# Wash_Basin_Indicator.net
KiCad netlist of a schematic drawn in EAGLE
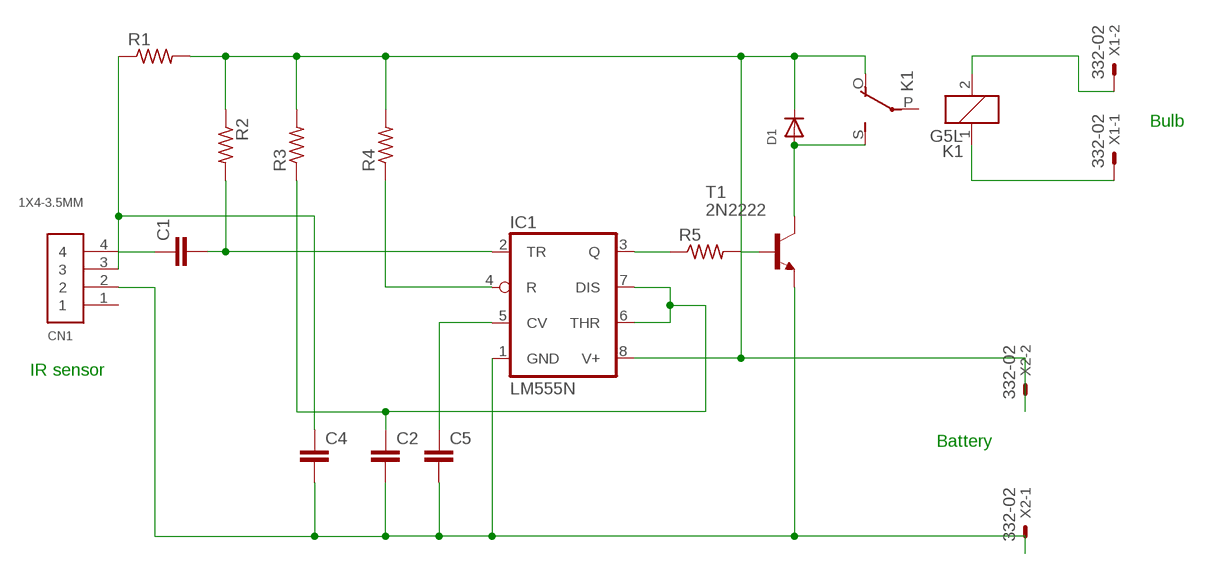
[diagram p0: schematic, sheet 1]

(export (version "E")
  (design (tool "Eeschema 10.0.6"))
  (components
    (comp (ref "C1")
      (value "C5/3.5")
      (footprint "eagle-import:C5B3.5")
      (libsource (lib "eagle-import") (part "C5/3.5"))
    )
    (comp (ref "C2")
      (value "C5/3.5")
      (footprint "eagle-import:C5B3.5")
      (libsource (lib "eagle-import") (part "C5/3.5"))
    )
    (comp (ref "C4")
      (value "C5/3.5")
      (footprint "eagle-import:C5B3.5")
      (libsource (lib "eagle-import") (part "C5/3.5"))
    )
    (comp (ref "C5")
      (value "C5/3.5")
      (footprint "eagle-import:C5B3.5")
      (libsource (lib "eagle-import") (part "C5/3.5"))
    )
    (comp (ref "CN1")
      (value "1X4-3.5MM")
      (footprint "eagle-import:1X04-3.5MM")
      (libsource (lib "eagle-import") (part "1X4-3.5MM"))
    )
    (comp (ref "D1")
      (value "DIODEDO-1N4148")
      (footprint "eagle-import:DO-1N4148")
      (libsource (lib "eagle-import") (part "DIODEDO-1N4148"))
    )
    (comp (ref "IC1")
      (value "LM555N")
      (footprint "eagle-import:DIL08")
      (libsource (lib "eagle-import") (part "555NLM"))
    )
    (comp (ref "K1")
      (value "G5L")
      (footprint "eagle-import:G5LE")
      (libsource (lib "eagle-import") (part "G5L"))
    )
    (comp (ref "R1")
      (value "R-US_0204/7")
      (footprint "eagle-import:0204_7")
      (libsource (lib "eagle-import") (part "R-US_0204/7"))
    )
    (comp (ref "R2")
      (value "R-US_0204/7")
      (footprint "eagle-import:0204_7")
      (libsource (lib "eagle-import") (part "R-US_0204/7"))
    )
    (comp (ref "R3")
      (value "R-US_0204/7")
      (footprint "eagle-import:0204_7")
      (libsource (lib "eagle-import") (part "R-US_0204/7"))
    )
    (comp (ref "R4")
      (value "R-US_0204/7")
      (footprint "eagle-import:0204_7")
      (libsource (lib "eagle-import") (part "R-US_0204/7"))
    )
    (comp (ref "R5")
      (value "R-US_0204/7")
      (footprint "eagle-import:0204_7")
      (libsource (lib "eagle-import") (part "R-US_0204/7"))
    )
    (comp (ref "T1")
      (value "2N2222")
      (footprint "eagle-import:TO92-EBC-OVAL")
      (libsource (lib "eagle-import") (part "2N2222"))
    )
    (comp (ref "X1")
      (value "332-02")
      (footprint "eagle-import:332-02")
      (libsource (lib "eagle-import") (part "332-02"))
    )
    (comp (ref "X2")
      (value "332-02")
      (footprint "eagle-import:332-02")
      (libsource (lib "eagle-import") (part "332-02"))
    )
  )
  (nets
    (net (code "1") (name "Net-(C1-Pad1)") (class "Default")
      (node (ref "C1") (pin "1") (pinfunction "1_1") (pintype "passive"))
      (node (ref "CN1") (pin "4") (pinfunction "4_4") (pintype "bidirectional"))
    )
    (net (code "2") (name "Net-(C4-Pad1)") (class "Default")
      (node (ref "C4") (pin "1") (pinfunction "1_1") (pintype "passive"))
      (node (ref "CN1") (pin "3") (pinfunction "3_3") (pintype "bidirectional"))
      (node (ref "R1") (pin "1") (pinfunction "1_1") (pintype "passive"))
    )
    (net (code "3") (name "Net-(D1-PadA)") (class "Default")
      (node (ref "D1") (pin "A") (pinfunction "A_A") (pintype "passive"))
      (node (ref "K1") (pin "S") (pinfunction "S_S") (pintype "passive"))
      (node (ref "T1") (pin "C") (pinfunction "C_C") (pintype "passive"))
    )
    (net (code "4") (name "Net-(IC1-CV)") (class "Default")
      (node (ref "C5") (pin "1") (pinfunction "1_1") (pintype "passive"))
      (node (ref "IC1") (pin "5") (pinfunction "CV_5") (pintype "input"))
    )
    (net (code "5") (name "Net-(IC1-DIS)") (class "Default")
      (node (ref "C2") (pin "1") (pinfunction "1_1") (pintype "passive"))
      (node (ref "IC1") (pin "6") (pinfunction "THR_6") (pintype "input"))
      (node (ref "IC1") (pin "7") (pinfunction "DIS_7") (pintype "input"))
      (node (ref "R3") (pin "1") (pinfunction "1_1") (pintype "passive"))
    )
    (net (code "6") (name "Net-(IC1-GND)") (class "Default")
      (node (ref "C2") (pin "2") (pinfunction "2_2") (pintype "passive"))
      (node (ref "C4") (pin "2") (pinfunction "2_2") (pintype "passive"))
      (node (ref "C5") (pin "2") (pinfunction "2_2") (pintype "passive"))
      (node (ref "CN1") (pin "2") (pinfunction "2_2") (pintype "bidirectional"))
      (node (ref "IC1") (pin "1") (pinfunction "GND_1") (pintype "power_in"))
      (node (ref "T1") (pin "E") (pinfunction "E_E") (pintype "passive"))
      (node (ref "X2") (pin "1") (pinfunction "S_1") (pintype "passive"))
    )
    (net (code "7") (name "Net-(IC1-Q)") (class "Default")
      (node (ref "IC1") (pin "3") (pinfunction "Q_3") (pintype "output"))
      (node (ref "R5") (pin "1") (pinfunction "1_1") (pintype "passive"))
    )
    (net (code "8") (name "Net-(IC1-R)") (class "Default")
      (node (ref "IC1") (pin "4") (pinfunction "R_4") (pintype "input"))
      (node (ref "R4") (pin "1") (pinfunction "1_1") (pintype "passive"))
    )
    (net (code "9") (name "Net-(IC1-TR)") (class "Default")
      (node (ref "C1") (pin "2") (pinfunction "2_2") (pintype "passive"))
      (node (ref "IC1") (pin "2") (pinfunction "TR_2") (pintype "input"))
      (node (ref "R2") (pin "2") (pinfunction "2_2") (pintype "passive"))
    )
    (net (code "10") (name "Net-(IC1-V+)") (class "Default")
      (node (ref "D1") (pin "C") (pinfunction "C_C") (pintype "passive"))
      (node (ref "IC1") (pin "8") (pinfunction "V+_8") (pintype "power_in"))
      (node (ref "K1") (pin "O") (pinfunction "O_O") (pintype "passive"))
      (node (ref "R1") (pin "2") (pinfunction "2_2") (pintype "passive"))
      (node (ref "R2") (pin "1") (pinfunction "1_1") (pintype "passive"))
      (node (ref "R3") (pin "2") (pinfunction "2_2") (pintype "passive"))
      (node (ref "R4") (pin "2") (pinfunction "2_2") (pintype "passive"))
      (node (ref "X2") (pin "2") (pinfunction "S_2") (pintype "passive"))
    )
    (net (code "11") (name "Net-(R5-Pad2)") (class "Default")
      (node (ref "R5") (pin "2") (pinfunction "2_2") (pintype "passive"))
      (node (ref "T1") (pin "B") (pinfunction "B_B") (pintype "passive"))
    )
    (net (code "12") (name "Net-(X1A-S)") (class "Default")
      (node (ref "K1") (pin "1") (pinfunction "1_1") (pintype "passive"))
      (node (ref "X1") (pin "1") (pinfunction "S_1") (pintype "passive"))
    )
    (net (code "13") (name "Net-(X1B-S)") (class "Default")
      (node (ref "K1") (pin "2") (pinfunction "2_2") (pintype "passive"))
      (node (ref "X1") (pin "2") (pinfunction "S_2") (pintype "passive"))
    )
    (net (code "14") (name "unconnected-(CN1-Pad1)") (class "Default")
      (node (ref "CN1") (pin "1") (pinfunction "1_1") (pintype "bidirectional"))
    )
    (net (code "15") (name "unconnected-(K1-PadP)") (class "Default")
      (node (ref "K1") (pin "P") (pinfunction "P_P") (pintype "passive"))
    )
  )
)
